# CLK_src_sys_logic.net
KiCad netlist of a schematic drawn in Altium Designer
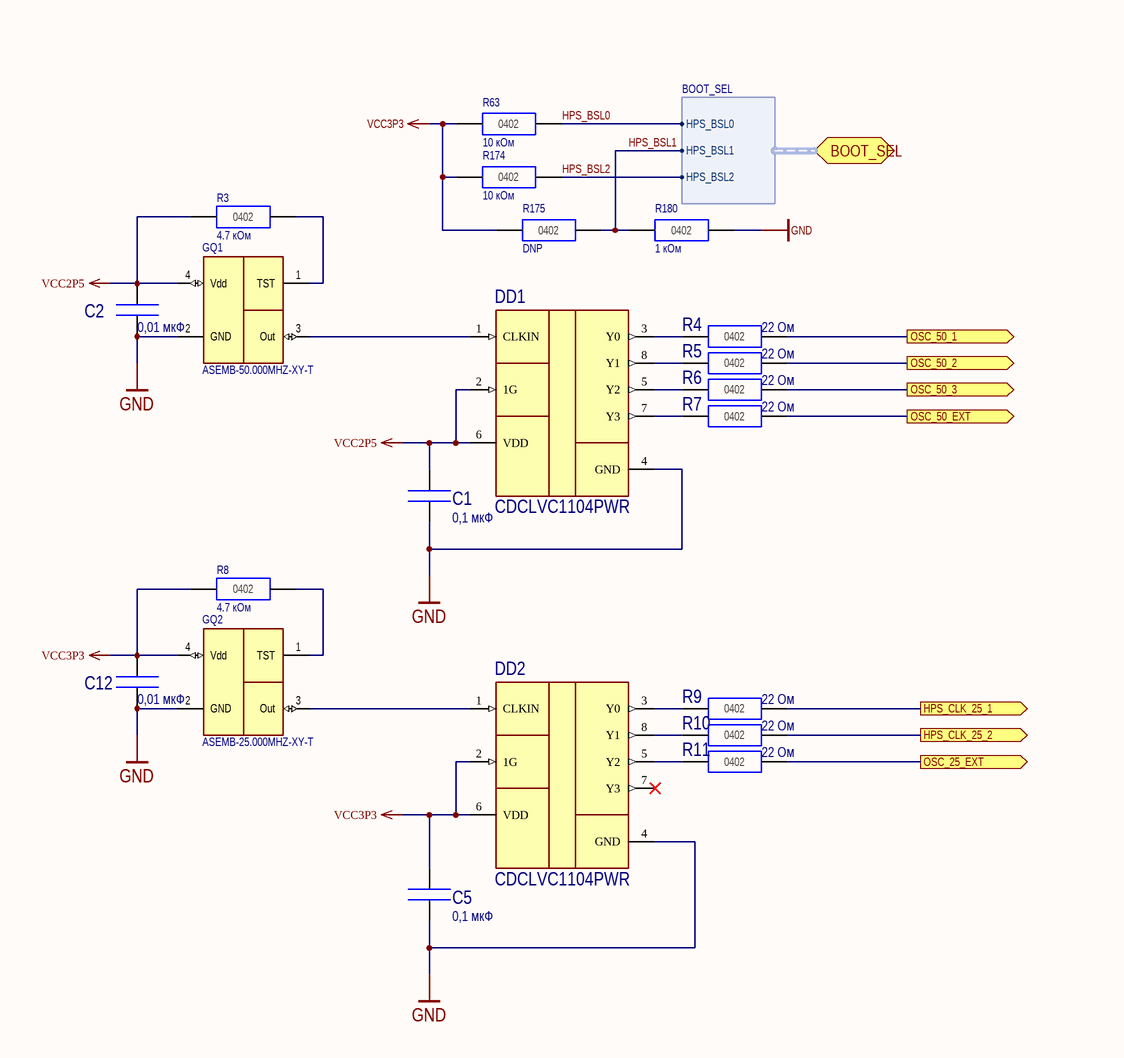
[diagram p0: CLK_src&sys_logic.SchDoc, left]
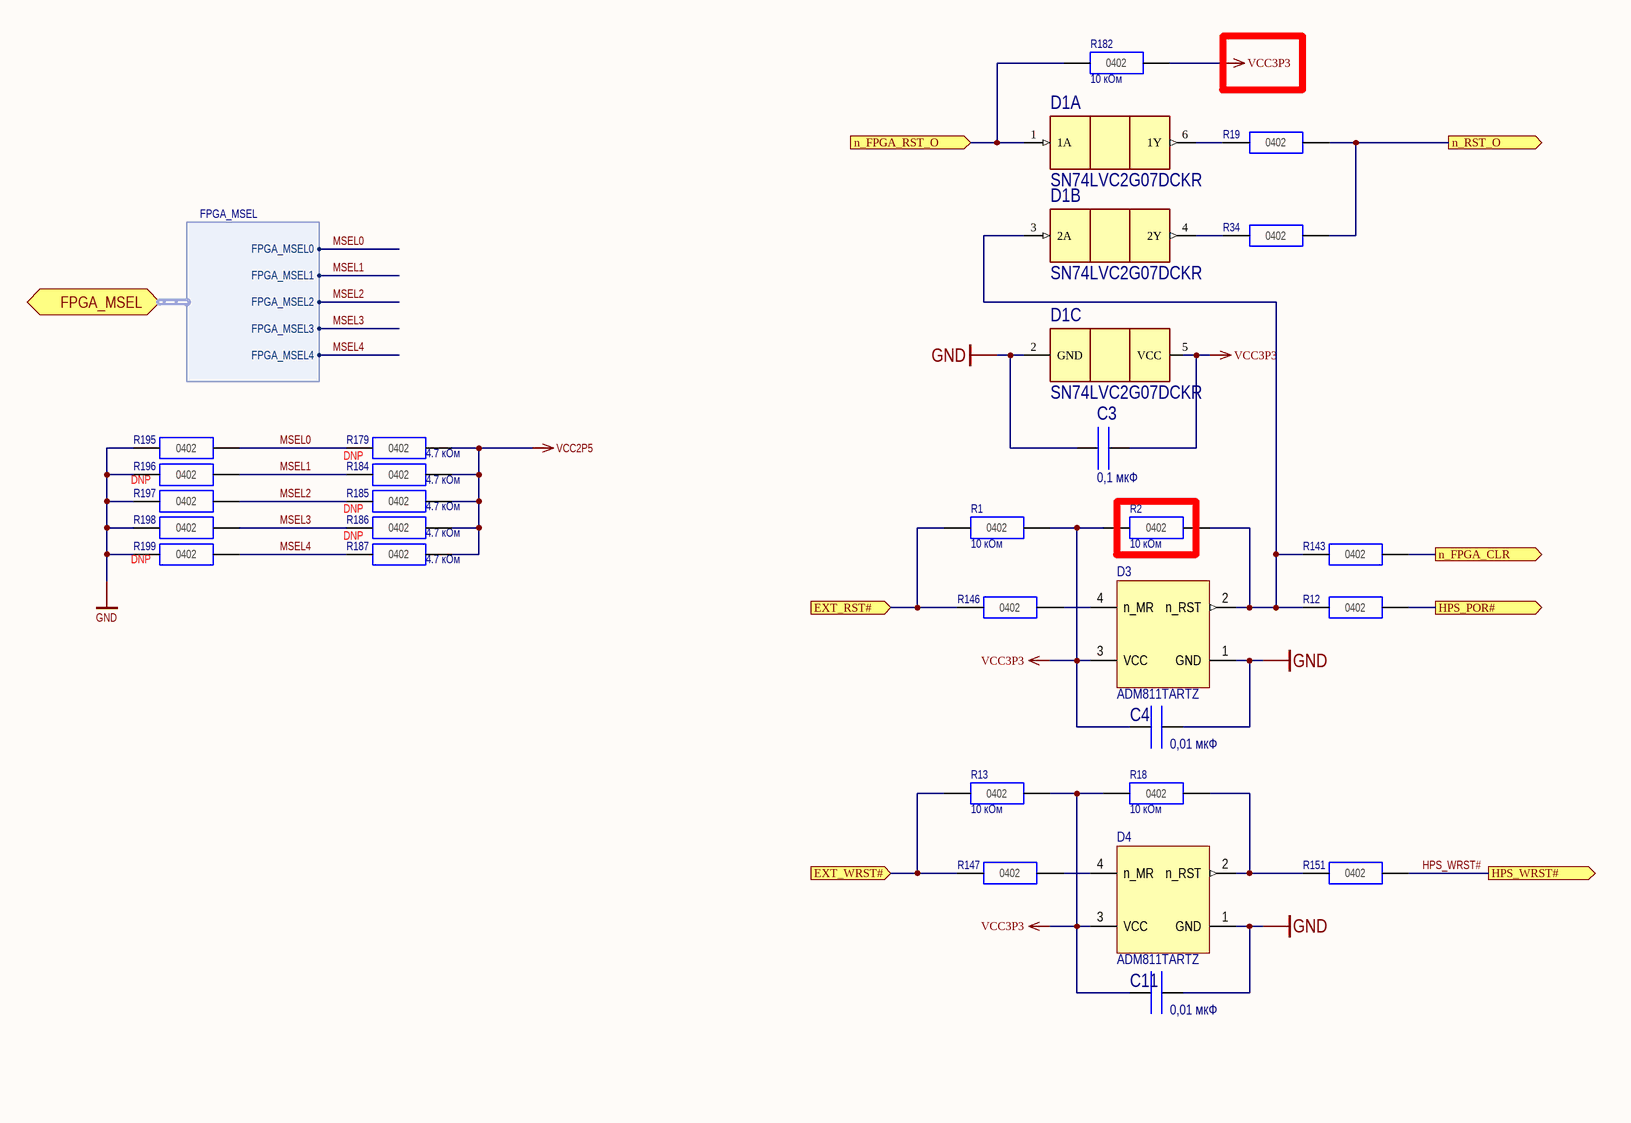
[diagram p1: CLK_src&sys_logic.SchDoc, right]

(export (version "E")
  (design (tool "Eeschema 10.0.6"))
  (components
    (comp (ref "C1")
      (value "0,1 мкФ")
      (footprint "CC0402(1005)")
      (description "Чип конденсатор керамический")
      (fields (field (name "Comment") "CC0402-X7R-0,1 мкФ-20%-10В"))
      (libsource (lib "Чип конденсаторы") (part "CC0402-X7R-#-20%-10В"))
    )
    (comp (ref "C2")
      (value "0,01 мкФ")
      (footprint "CC0402(1005)")
      (description "Чип конденсатор керамический")
      (fields (field (name "Comment") "CC0402-X7R-0,01 мкФ-10%-50В"))
      (libsource (lib "Чип конденсаторы") (part "CC0402-X7R-#-20%-10В"))
    )
    (comp (ref "C3")
      (value "0,1 мкФ")
      (footprint "CC0402(1005)")
      (description "Чип конденсатор керамический")
      (fields (field (name "Comment") "CC0402-X7R-0,1 мкФ-20%-10В"))
      (libsource (lib "Чип конденсаторы") (part "CC0402-X7R-#-20%-10В"))
    )
    (comp (ref "C4")
      (value "0,01 мкФ")
      (footprint "CC0402(1005)")
      (description "Чип конденсатор керамический")
      (fields (field (name "Comment") "CC0402-X7R-0,01 мкФ-10%-50В"))
      (libsource (lib "Чип конденсаторы") (part "CC0402-X7R-#-20%-10В"))
    )
    (comp (ref "C5")
      (value "0,1 мкФ")
      (footprint "CC0402(1005)")
      (description "Чип конденсатор керамический")
      (fields (field (name "Comment") "CC0402-X7R-0,1 мкФ-20%-10В"))
      (libsource (lib "Чип конденсаторы") (part "CC0402-X7R-#-20%-10В"))
    )
    (comp (ref "C11")
      (value "0,01 мкФ")
      (footprint "CC0402(1005)")
      (description "Чип конденсатор керамический")
      (fields (field (name "Comment") "CC0402-X7R-0,01 мкФ-10%-50В"))
      (libsource (lib "Чип конденсаторы") (part "CC0402-X7R-#-20%-10В"))
    )
    (comp (ref "C12")
      (value "0,01 мкФ")
      (footprint "CC0402(1005)")
      (description "Чип конденсатор керамический")
      (fields (field (name "Comment") "CC0402-X7R-0,01 мкФ-10%-50В"))
      (libsource (lib "Чип конденсаторы") (part "CC0402-X7R-#-20%-10В"))
    )
    (comp (ref "D1")
      (value "SN74LVC2G07DCKR")
      (footprint "DCKR")
      (description "Dual Buffer and Driver With Open-Drain Outputs")
      (libsource (lib "SD_IC") (part "IC_TI_SN74LVC2G07"))
    )
    (comp (ref "D3")
      (value "ADM811TARTZ")
      (footprint "SOT-143")
      (description "Microprocessor Supervisory Circuit in 3-Pin SOT-23")
      (fields (field (name "PUBLISHER") "Altium Limited"))
      (libsource (lib "SD_IC") (part "IC_AD_ADM811TARTZ"))
    )
    (comp (ref "D4")
      (value "ADM811TARTZ")
      (footprint "SOT-143")
      (description "Microprocessor Supervisory Circuit in 3-Pin SOT-23")
      (fields (field (name "PUBLISHER") "Altium Limited"))
      (libsource (lib "SD_IC") (part "IC_AD_ADM811TARTZ"))
    )
    (comp (ref "DD1")
      (value "CDCLVC1104PWR")
      (footprint "TSSOP-8")
      (description "High-Performance  Clock Buffer 1:4")
      (libsource (lib "Микросхемы") (part "CDCLVC1104PWR"))
    )
    (comp (ref "DD2")
      (value "CDCLVC1104PWR")
      (footprint "TSSOP-8")
      (description "High-Performance  Clock Buffer 1:4")
      (libsource (lib "Микросхемы") (part "CDCLVC1104PWR"))
    )
    (comp (ref "GQ1")
      (value "ASEMB-50.000MHZ-XY-T")
      (footprint "DFN210P320X100-4N")
      (description "Dual High Side Switch With OC_DET 500mA/CH")
      (fields (field (name "MANUFACTURER PART NO.") "ASEMB-50.000MHZ-XY-T"))
      (libsource (lib "SD_IC") (part "OSC-ABRCN-ASE3"))
    )
    (comp (ref "GQ2")
      (value "ASEMB-25.000MHZ-XY-T")
      (footprint "DFN210P320X100-4N")
      (description "Dual High Side Switch With OC_DET 500mA/CH")
      (fields (field (name "MANUFACTURER PART NO.") "ASEMB-25.000MHZ-XY-T"))
      (libsource (lib "SD_IC") (part "OSC-ABRCN-ASE3"))
    )
    (comp (ref "R1")
      (value "10 кОм")
      (footprint "CR0402(1005)")
      (description "Чип резистор")
      (fields (field (name "TOLERANCE") "5%") (field (name "Comment") "CR0402-10 кОм-±5%"))
      (libsource (lib "Резисторы") (part "CR0402-#-±5%"))
    )
    (comp (ref "R2")
      (value "10 кОм")
      (footprint "CR0402(1005)")
      (description "Чип резистор")
      (fields (field (name "TOLERANCE") "5%") (field (name "Comment") "CR0402-10 кОм-±5%"))
      (libsource (lib "Резисторы") (part "CR0402-#-±5%"))
    )
    (comp (ref "R3")
      (value "4.7 кОм")
      (footprint "CR0402(1005)")
      (description "Чип резистор")
      (fields (field (name "TOLERANCE") "5%") (field (name "Comment") "CR0402-4.7 кОм-±5%"))
      (libsource (lib "Резисторы") (part "CR0402-#-±5%"))
    )
    (comp (ref "R4")
      (value "22 Ом")
      (footprint "CR0402(1005)")
      (description "Чип резистор")
      (fields (field (name "TOLERANCE") "5%") (field (name "Comment") "CR0402-22 Ом-±5%"))
      (libsource (lib "Чип резисторы") (part "CR0402-#-±5%"))
    )
    (comp (ref "R5")
      (value "22 Ом")
      (footprint "CR0402(1005)")
      (description "Чип резистор")
      (fields (field (name "TOLERANCE") "5%") (field (name "Comment") "CR0402-22 Ом-±5%"))
      (libsource (lib "Чип резисторы") (part "CR0402-#-±5%"))
    )
    (comp (ref "R6")
      (value "22 Ом")
      (footprint "CR0402(1005)")
      (description "Чип резистор")
      (fields (field (name "TOLERANCE") "5%") (field (name "Comment") "CR0402-22 Ом-±5%"))
      (libsource (lib "Чип резисторы") (part "CR0402-#-±5%"))
    )
    (comp (ref "R7")
      (value "22 Ом")
      (footprint "CR0402(1005)")
      (description "Чип резистор")
      (fields (field (name "TOLERANCE") "5%") (field (name "Comment") "CR0402-22 Ом-±5%"))
      (libsource (lib "Чип резисторы") (part "CR0402-#-±5%"))
    )
    (comp (ref "R8")
      (value "4.7 кОм")
      (footprint "CR0402(1005)")
      (description "Чип резистор")
      (fields (field (name "TOLERANCE") "5%") (field (name "Comment") "CR0402-4.7 кОм-±5%"))
      (libsource (lib "Резисторы") (part "CR0402-#-±5%"))
    )
    (comp (ref "R9")
      (value "22 Ом")
      (footprint "CR0402(1005)")
      (description "Чип резистор")
      (fields (field (name "TOLERANCE") "5%") (field (name "Comment") "CR0402-22 Ом-±5%"))
      (libsource (lib "Чип резисторы") (part "CR0402-#-±5%"))
    )
    (comp (ref "R10")
      (value "22 Ом")
      (footprint "CR0402(1005)")
      (description "Чип резистор")
      (fields (field (name "TOLERANCE") "5%") (field (name "Comment") "CR0402-22 Ом-±5%"))
      (libsource (lib "Чип резисторы") (part "CR0402-#-±5%"))
    )
    (comp (ref "R11")
      (value "22 Ом")
      (footprint "CR0402(1005)")
      (description "Чип резистор")
      (fields (field (name "TOLERANCE") "5%") (field (name "Comment") "CR0402-22 Ом-±5%"))
      (libsource (lib "Чип резисторы") (part "CR0402-#-±5%"))
    )
    (comp (ref "R12")
      (value "CR0402-0 Ом-±5%")
      (footprint "CR0402(1005)")
      (description "Чип резистор")
      (fields (field (name "TOLERANCE") "5%"))
      (libsource (lib "Резисторы") (part "CR0402-#-±5%"))
    )
    (comp (ref "R13")
      (value "10 кОм")
      (footprint "CR0402(1005)")
      (description "Чип резистор")
      (fields (field (name "TOLERANCE") "5%") (field (name "Comment") "CR0402-10 кОм-±5%"))
      (libsource (lib "Резисторы") (part "CR0402-#-±5%"))
    )
    (comp (ref "R18")
      (value "10 кОм")
      (footprint "CR0402(1005)")
      (description "Чип резистор")
      (fields (field (name "TOLERANCE") "5%") (field (name "Comment") "CR0402-10 кОм-±5%"))
      (libsource (lib "Резисторы") (part "CR0402-#-±5%"))
    )
    (comp (ref "R19")
      (value "CR0402-0 Ом-±5%")
      (footprint "CR0402(1005)")
      (description "Чип резистор")
      (fields (field (name "TOLERANCE") "5%"))
      (libsource (lib "Резисторы") (part "CR0402-#-±5%"))
    )
    (comp (ref "R34")
      (value "CR0402-0 Ом-±5%")
      (footprint "CR0402(1005)")
      (description "Чип резистор")
      (fields (field (name "TOLERANCE") "5%"))
      (libsource (lib "Резисторы") (part "CR0402-#-±5%"))
    )
    (comp (ref "R63")
      (value "10 кОм")
      (footprint "CR0402(1005)_OCT")
      (description "Чип резистор")
      (fields (field (name "TOLERANCE") "5%") (field (name "Comment") "CR0402-10 кОм-±5%"))
      (libsource (lib "Резисторы") (part "CR0402-#-±5%"))
    )
    (comp (ref "R143")
      (value "CR0402-0 Ом-±5%")
      (footprint "CR0402(1005)")
      (description "Чип резистор")
      (fields (field (name "TOLERANCE") "5%"))
      (libsource (lib "Резисторы") (part "CR0402-#-±5%"))
    )
    (comp (ref "R146")
      (value "CR0402-0 Ом-±5%")
      (footprint "CR0402(1005)")
      (description "Чип резистор")
      (fields (field (name "TOLERANCE") "5%"))
      (libsource (lib "Резисторы") (part "CR0402-#-±5%"))
    )
    (comp (ref "R147")
      (value "CR0402-0 Ом-±5%")
      (footprint "CR0402(1005)")
      (description "Чип резистор")
      (fields (field (name "TOLERANCE") "5%"))
      (libsource (lib "Резисторы") (part "CR0402-#-±5%"))
    )
    (comp (ref "R151")
      (value "CR0402-0 Ом-±5%")
      (footprint "CR0402(1005)")
      (description "Чип резистор")
      (fields (field (name "TOLERANCE") "5%"))
      (libsource (lib "Резисторы") (part "CR0402-#-±5%"))
    )
    (comp (ref "R174")
      (value "10 кОм")
      (footprint "CR0402(1005)_OCT")
      (description "Чип резистор")
      (fields (field (name "TOLERANCE") "5%") (field (name "Comment") "CR0402-10 кОм-±5%"))
      (libsource (lib "Резисторы") (part "CR0402-#-±5%"))
    )
    (comp (ref "R175")
      (value "DNP")
      (footprint "CR0402(1005)")
      (description "Чип резистор")
      (fields (field (name "TOLERANCE") "5%") (field (name "Comment") "CR0402-DNP-±5%"))
      (libsource (lib "Резисторы") (part "CR0402-#-±5%"))
    )
    (comp (ref "R179")
      (value "4.7 кОм")
      (footprint "CR0402(1005)_OCT")
      (description "Чип резистор")
      (fields
        (field (name "TOLERANCE") "5%")
        (field (name "PLACE") "DNP")
        (field (name "Comment") "CR0402-4.7 кОм-±5%")
      )
      (libsource (lib "Резисторы") (part "CR0402-#-±5%"))
    )
    (comp (ref "R180")
      (value "1 кОм")
      (footprint "CR0402(1005)")
      (description "Чип резистор")
      (fields (field (name "TOLERANCE") "5%") (field (name "Comment") "CR0402-1 кОм-±5%"))
      (libsource (lib "Резисторы") (part "CR0402-#-±5%"))
    )
    (comp (ref "R182")
      (value "10 кОм")
      (footprint "CR0402(1005)")
      (description "Чип резистор")
      (fields (field (name "TOLERANCE") "5%") (field (name "Comment") "CR0402-10 кОм-±5%"))
      (libsource (lib "Резисторы") (part "CR0402-#-±5%"))
    )
    (comp (ref "R184")
      (value "4.7 кОм")
      (footprint "CR0402(1005)_OCT")
      (description "Чип резистор")
      (fields (field (name "TOLERANCE") "5%") (field (name "Comment") "CR0402-4.7 кОм-±5%"))
      (libsource (lib "Резисторы") (part "CR0402-#-±5%"))
    )
    (comp (ref "R185")
      (value "4.7 кОм")
      (footprint "CR0402(1005)")
      (description "Чип резистор")
      (fields
        (field (name "TOLERANCE") "5%")
        (field (name "PLACE") "DNP")
        (field (name "Comment") "CR0402-4.7 кОм-±5%")
      )
      (libsource (lib "Резисторы") (part "CR0402-#-±5%"))
    )
    (comp (ref "R186")
      (value "4.7 кОм")
      (footprint "CR0402(1005)")
      (description "Чип резистор")
      (fields
        (field (name "TOLERANCE") "5%")
        (field (name "PLACE") "DNP")
        (field (name "Comment") "CR0402-4.7 кОм-±5%")
      )
      (libsource (lib "Резисторы") (part "CR0402-#-±5%"))
    )
    (comp (ref "R187")
      (value "4.7 кОм")
      (footprint "CR0402(1005)")
      (description "Чип резистор")
      (fields (field (name "TOLERANCE") "5%") (field (name "Comment") "CR0402-4.7 кОм-±5%"))
      (libsource (lib "Резисторы") (part "CR0402-#-±5%"))
    )
    (comp (ref "R195")
      (value "CR0402-0 Ом-±5%")
      (footprint "CR0402(1005)")
      (description "Чип резистор")
      (fields (field (name "TOLERANCE") "5%"))
      (libsource (lib "Резисторы") (part "CR0402-#-±5%"))
    )
    (comp (ref "R196")
      (value "CR0402-0 Ом-±5%")
      (footprint "CR0402(1005)")
      (description "Чип резистор")
      (fields (field (name "TOLERANCE") "5%") (field (name "PLACE") "DNP"))
      (libsource (lib "Резисторы") (part "CR0402-#-±5%"))
    )
    (comp (ref "R197")
      (value "CR0402-0 Ом-±5%")
      (footprint "CR0402(1005)")
      (description "Чип резистор")
      (fields (field (name "TOLERANCE") "5%"))
      (libsource (lib "Резисторы") (part "CR0402-#-±5%"))
    )
    (comp (ref "R198")
      (value "CR0402-0 Ом-±5%")
      (footprint "CR0402(1005)")
      (description "Чип резистор")
      (fields (field (name "TOLERANCE") "5%"))
      (libsource (lib "Резисторы") (part "CR0402-#-±5%"))
    )
    (comp (ref "R199")
      (value "CR0402-0 Ом-±5%")
      (footprint "CR0402(1005)")
      (description "Чип резистор")
      (fields (field (name "TOLERANCE") "5%") (field (name "PLACE") "DNP"))
      (libsource (lib "Резисторы") (part "CR0402-#-±5%"))
    )
  )
  (nets
    (net (code "3") (name "/EXT_RST#") (class "Default")
      (node (ref "R1") (pin "1") (pinfunction "+_1") (pintype "passive"))
      (node (ref "R146") (pin "1") (pinfunction "+_1") (pintype "passive"))
    )
    (net (code "4") (name "/EXT_WRST#") (class "Default")
      (node (ref "R13") (pin "1") (pinfunction "+_1") (pintype "passive"))
      (node (ref "R147") (pin "1") (pinfunction "+_1") (pintype "passive"))
    )
    (net (code "5") (name "/HPS_BSL0") (class "Default")
      (node (ref "R63") (pin "2") (pinfunction "-_2") (pintype "passive"))
    )
    (net (code "6") (name "/HPS_BSL1") (class "Default")
      (node (ref "R175") (pin "2") (pinfunction "-_2") (pintype "passive"))
      (node (ref "R180") (pin "1") (pinfunction "+_1") (pintype "passive"))
    )
    (net (code "7") (name "/HPS_BSL2") (class "Default")
      (node (ref "R174") (pin "2") (pinfunction "-_2") (pintype "passive"))
    )
    (net (code "8") (name "/HPS_CLK_25_1") (class "Default")
      (node (ref "R9") (pin "2") (pinfunction "-_2") (pintype "passive"))
    )
    (net (code "9") (name "/HPS_CLK_25_2") (class "Default")
      (node (ref "R10") (pin "2") (pinfunction "-_2") (pintype "passive"))
    )
    (net (code "10") (name "/HPS_POR#") (class "Default")
      (node (ref "R12") (pin "2") (pinfunction "-_2") (pintype "passive"))
    )
    (net (code "11") (name "/HPS_WRST#") (class "Default")
      (node (ref "R151") (pin "2") (pinfunction "-_2") (pintype "passive"))
    )
    (net (code "12") (name "/MSEL0") (class "Default")
      (node (ref "R179") (pin "1") (pinfunction "+_1") (pintype "passive"))
      (node (ref "R195") (pin "2") (pinfunction "-_2") (pintype "passive"))
    )
    (net (code "13") (name "/MSEL1") (class "Default")
      (node (ref "R184") (pin "1") (pinfunction "+_1") (pintype "passive"))
      (node (ref "R196") (pin "2") (pinfunction "-_2") (pintype "passive"))
    )
    (net (code "14") (name "/MSEL2") (class "Default")
      (node (ref "R185") (pin "1") (pinfunction "+_1") (pintype "passive"))
      (node (ref "R197") (pin "2") (pinfunction "-_2") (pintype "passive"))
    )
    (net (code "15") (name "/MSEL3") (class "Default")
      (node (ref "R186") (pin "1") (pinfunction "+_1") (pintype "passive"))
      (node (ref "R198") (pin "2") (pinfunction "-_2") (pintype "passive"))
    )
    (net (code "16") (name "/MSEL4") (class "Default")
      (node (ref "R187") (pin "1") (pinfunction "+_1") (pintype "passive"))
      (node (ref "R199") (pin "2") (pinfunction "-_2") (pintype "passive"))
    )
    (net (code "17") (name "/OSC_25_EXT") (class "Default")
      (node (ref "R11") (pin "2") (pinfunction "-_2") (pintype "passive"))
    )
    (net (code "18") (name "/OSC_50_1") (class "Default")
      (node (ref "R4") (pin "2") (pinfunction "-_2") (pintype "passive"))
    )
    (net (code "19") (name "/OSC_50_2") (class "Default")
      (node (ref "R5") (pin "2") (pinfunction "-_2") (pintype "passive"))
    )
    (net (code "20") (name "/OSC_50_3") (class "Default")
      (node (ref "R6") (pin "2") (pinfunction "-_2") (pintype "passive"))
    )
    (net (code "21") (name "/OSC_50_EXT") (class "Default")
      (node (ref "R7") (pin "2") (pinfunction "-_2") (pintype "passive"))
    )
    (net (code "22") (name "/n_FPGA_CLR") (class "Default")
      (node (ref "R143") (pin "2") (pinfunction "-_2") (pintype "passive"))
    )
    (net (code "23") (name "/n_FPGA_RST_O") (class "Default")
      (node (ref "D1") (pin "1") (pinfunction "1A_1") (pintype "input"))
      (node (ref "R182") (pin "1") (pinfunction "+_1") (pintype "passive"))
    )
    (net (code "24") (name "/n_RST_O") (class "Default")
      (node (ref "R19") (pin "2") (pinfunction "-_2") (pintype "passive"))
      (node (ref "R34") (pin "2") (pinfunction "-_2") (pintype "passive"))
    )
    (net (code "27") (name "GND") (class "Default")
      (node (ref "C1") (pin "2") (pinfunction "-_2") (pintype "passive"))
      (node (ref "C11") (pin "1") (pinfunction "+_1") (pintype "passive"))
      (node (ref "C12") (pin "1") (pinfunction "+_1") (pintype "passive"))
      (node (ref "C2") (pin "1") (pinfunction "+_1") (pintype "passive"))
      (node (ref "C3") (pin "1") (pinfunction "+_1") (pintype "passive"))
      (node (ref "C4") (pin "1") (pinfunction "+_1") (pintype "passive"))
      (node (ref "C5") (pin "2") (pinfunction "-_2") (pintype "passive"))
      (node (ref "D1") (pin "2") (pinfunction "GND_2") (pintype "power_in"))
      (node (ref "D3") (pin "1") (pinfunction "GND_1") (pintype "power_in"))
      (node (ref "D4") (pin "1") (pinfunction "GND_1") (pintype "power_in"))
      (node (ref "DD1") (pin "4") (pinfunction "GND_4") (pintype "power_in"))
      (node (ref "DD2") (pin "4") (pinfunction "GND_4") (pintype "power_in"))
      (node (ref "GQ1") (pin "2") (pinfunction "GND_2") (pintype "power_in"))
      (node (ref "GQ2") (pin "2") (pinfunction "GND_2") (pintype "power_in"))
      (node (ref "R180") (pin "2") (pinfunction "-_2") (pintype "passive"))
      (node (ref "R195") (pin "1") (pinfunction "+_1") (pintype "passive"))
      (node (ref "R196") (pin "1") (pinfunction "+_1") (pintype "passive"))
      (node (ref "R197") (pin "1") (pinfunction "+_1") (pintype "passive"))
      (node (ref "R198") (pin "1") (pinfunction "+_1") (pintype "passive"))
      (node (ref "R199") (pin "1") (pinfunction "+_1") (pintype "passive"))
    )
    (net (code "28") (name "Net-(D1A-1Y)") (class "Default")
      (node (ref "D1") (pin "6") (pinfunction "1Y_6") (pintype "output"))
      (node (ref "R19") (pin "1") (pinfunction "+_1") (pintype "passive"))
    )
    (net (code "29") (name "Net-(D1B-2A)") (class "Default")
      (node (ref "D1") (pin "3") (pinfunction "2A_3") (pintype "input"))
      (node (ref "D3") (pin "2") (pinfunction "n_RST_2") (pintype "output"))
      (node (ref "R12") (pin "1") (pinfunction "+_1") (pintype "passive"))
      (node (ref "R143") (pin "1") (pinfunction "+_1") (pintype "passive"))
      (node (ref "R2") (pin "2") (pinfunction "-_2") (pintype "passive"))
    )
    (net (code "30") (name "Net-(D1B-2Y)") (class "Default")
      (node (ref "D1") (pin "4") (pinfunction "2Y_4") (pintype "output"))
      (node (ref "R34") (pin "1") (pinfunction "+_1") (pintype "passive"))
    )
    (net (code "31") (name "Net-(D3-n_MR)") (class "Default")
      (node (ref "D3") (pin "4") (pinfunction "n_MR_4") (pintype "power_in"))
      (node (ref "R146") (pin "2") (pinfunction "-_2") (pintype "passive"))
    )
    (net (code "32") (name "Net-(D4-n_MR)") (class "Default")
      (node (ref "D4") (pin "4") (pinfunction "n_MR_4") (pintype "power_in"))
      (node (ref "R147") (pin "2") (pinfunction "-_2") (pintype "passive"))
    )
    (net (code "33") (name "Net-(D4-n_RST)") (class "Default")
      (node (ref "D4") (pin "2") (pinfunction "n_RST_2") (pintype "output"))
      (node (ref "R151") (pin "1") (pinfunction "+_1") (pintype "passive"))
      (node (ref "R18") (pin "2") (pinfunction "-_2") (pintype "passive"))
    )
    (net (code "34") (name "Net-(DD1-CLKIN)") (class "Default")
      (node (ref "DD1") (pin "1") (pinfunction "CLKIN_1") (pintype "input"))
      (node (ref "GQ1") (pin "3") (pinfunction "Out_3") (pintype "bidirectional"))
    )
    (net (code "35") (name "Net-(DD1-Y0)") (class "Default")
      (node (ref "DD1") (pin "3") (pinfunction "Y0_3") (pintype "output"))
      (node (ref "R4") (pin "1") (pinfunction "+_1") (pintype "passive"))
    )
    (net (code "36") (name "Net-(DD1-Y1)") (class "Default")
      (node (ref "DD1") (pin "8") (pinfunction "Y1_8") (pintype "output"))
      (node (ref "R5") (pin "1") (pinfunction "+_1") (pintype "passive"))
    )
    (net (code "37") (name "Net-(DD1-Y2)") (class "Default")
      (node (ref "DD1") (pin "5") (pinfunction "Y2_5") (pintype "output"))
      (node (ref "R6") (pin "1") (pinfunction "+_1") (pintype "passive"))
    )
    (net (code "38") (name "Net-(DD1-Y3)") (class "Default")
      (node (ref "DD1") (pin "7") (pinfunction "Y3_7") (pintype "output"))
      (node (ref "R7") (pin "1") (pinfunction "+_1") (pintype "passive"))
    )
    (net (code "39") (name "Net-(DD2-CLKIN)") (class "Default")
      (node (ref "DD2") (pin "1") (pinfunction "CLKIN_1") (pintype "input"))
      (node (ref "GQ2") (pin "3") (pinfunction "Out_3") (pintype "bidirectional"))
    )
    (net (code "40") (name "Net-(DD2-Y0)") (class "Default")
      (node (ref "DD2") (pin "3") (pinfunction "Y0_3") (pintype "output"))
      (node (ref "R9") (pin "1") (pinfunction "+_1") (pintype "passive"))
    )
    (net (code "41") (name "Net-(DD2-Y1)") (class "Default")
      (node (ref "DD2") (pin "8") (pinfunction "Y1_8") (pintype "output"))
      (node (ref "R10") (pin "1") (pinfunction "+_1") (pintype "passive"))
    )
    (net (code "42") (name "Net-(DD2-Y2)") (class "Default")
      (node (ref "DD2") (pin "5") (pinfunction "Y2_5") (pintype "output"))
      (node (ref "R11") (pin "1") (pinfunction "+_1") (pintype "passive"))
    )
    (net (code "43") (name "Net-(GQ1-TST)") (class "Default")
      (node (ref "GQ1") (pin "1") (pinfunction "TST_1") (pintype "power_in"))
      (node (ref "R3") (pin "2") (pinfunction "-_2") (pintype "passive"))
    )
    (net (code "44") (name "Net-(GQ2-TST)") (class "Default")
      (node (ref "GQ2") (pin "1") (pinfunction "TST_1") (pintype "power_in"))
      (node (ref "R8") (pin "2") (pinfunction "-_2") (pintype "passive"))
    )
    (net (code "45") (name "VCC2P5") (class "Default")
      (node (ref "C1") (pin "1") (pinfunction "+_1") (pintype "passive"))
      (node (ref "C2") (pin "2") (pinfunction "-_2") (pintype "passive"))
      (node (ref "DD1") (pin "2") (pinfunction "1G_2") (pintype "input"))
      (node (ref "DD1") (pin "6") (pinfunction "VDD_6") (pintype "power_in"))
      (node (ref "GQ1") (pin "4") (pinfunction "Vdd_4") (pintype "bidirectional"))
      (node (ref "R179") (pin "2") (pinfunction "-_2") (pintype "passive"))
      (node (ref "R184") (pin "2") (pinfunction "-_2") (pintype "passive"))
      (node (ref "R185") (pin "2") (pinfunction "-_2") (pintype "passive"))
      (node (ref "R186") (pin "2") (pinfunction "-_2") (pintype "passive"))
      (node (ref "R187") (pin "2") (pinfunction "-_2") (pintype "passive"))
      (node (ref "R3") (pin "1") (pinfunction "+_1") (pintype "passive"))
    )
    (net (code "46") (name "VCC3P3") (class "Default")
      (node (ref "C11") (pin "2") (pinfunction "-_2") (pintype "passive"))
      (node (ref "C12") (pin "2") (pinfunction "-_2") (pintype "passive"))
      (node (ref "C3") (pin "2") (pinfunction "-_2") (pintype "passive"))
      (node (ref "C4") (pin "2") (pinfunction "-_2") (pintype "passive"))
      (node (ref "C5") (pin "1") (pinfunction "+_1") (pintype "passive"))
      (node (ref "D1") (pin "5") (pinfunction "VCC_5") (pintype "power_in"))
      (node (ref "D3") (pin "3") (pinfunction "VCC_3") (pintype "power_in"))
      (node (ref "D4") (pin "3") (pinfunction "VCC_3") (pintype "power_in"))
      (node (ref "DD2") (pin "2") (pinfunction "1G_2") (pintype "input"))
      (node (ref "DD2") (pin "6") (pinfunction "VDD_6") (pintype "power_in"))
      (node (ref "GQ2") (pin "4") (pinfunction "Vdd_4") (pintype "bidirectional"))
      (node (ref "R1") (pin "2") (pinfunction "-_2") (pintype "passive"))
      (node (ref "R13") (pin "2") (pinfunction "-_2") (pintype "passive"))
      (node (ref "R174") (pin "1") (pinfunction "+_1") (pintype "passive"))
      (node (ref "R175") (pin "1") (pinfunction "+_1") (pintype "passive"))
      (node (ref "R18") (pin "1") (pinfunction "+_1") (pintype "passive"))
      (node (ref "R182") (pin "2") (pinfunction "-_2") (pintype "passive"))
      (node (ref "R2") (pin "1") (pinfunction "+_1") (pintype "passive"))
      (node (ref "R63") (pin "1") (pinfunction "+_1") (pintype "passive"))
      (node (ref "R8") (pin "1") (pinfunction "+_1") (pintype "passive"))
    )
    (net (code "47") (name "unconnected-(DD2-Y3-Pad7)") (class "Default")
      (node (ref "DD2") (pin "7") (pinfunction "Y3_7") (pintype "output+no_connect"))
    )
  )
)
